# Sheet1_popravljena.net
KiCad netlist of a schematic drawn in Altium Designer
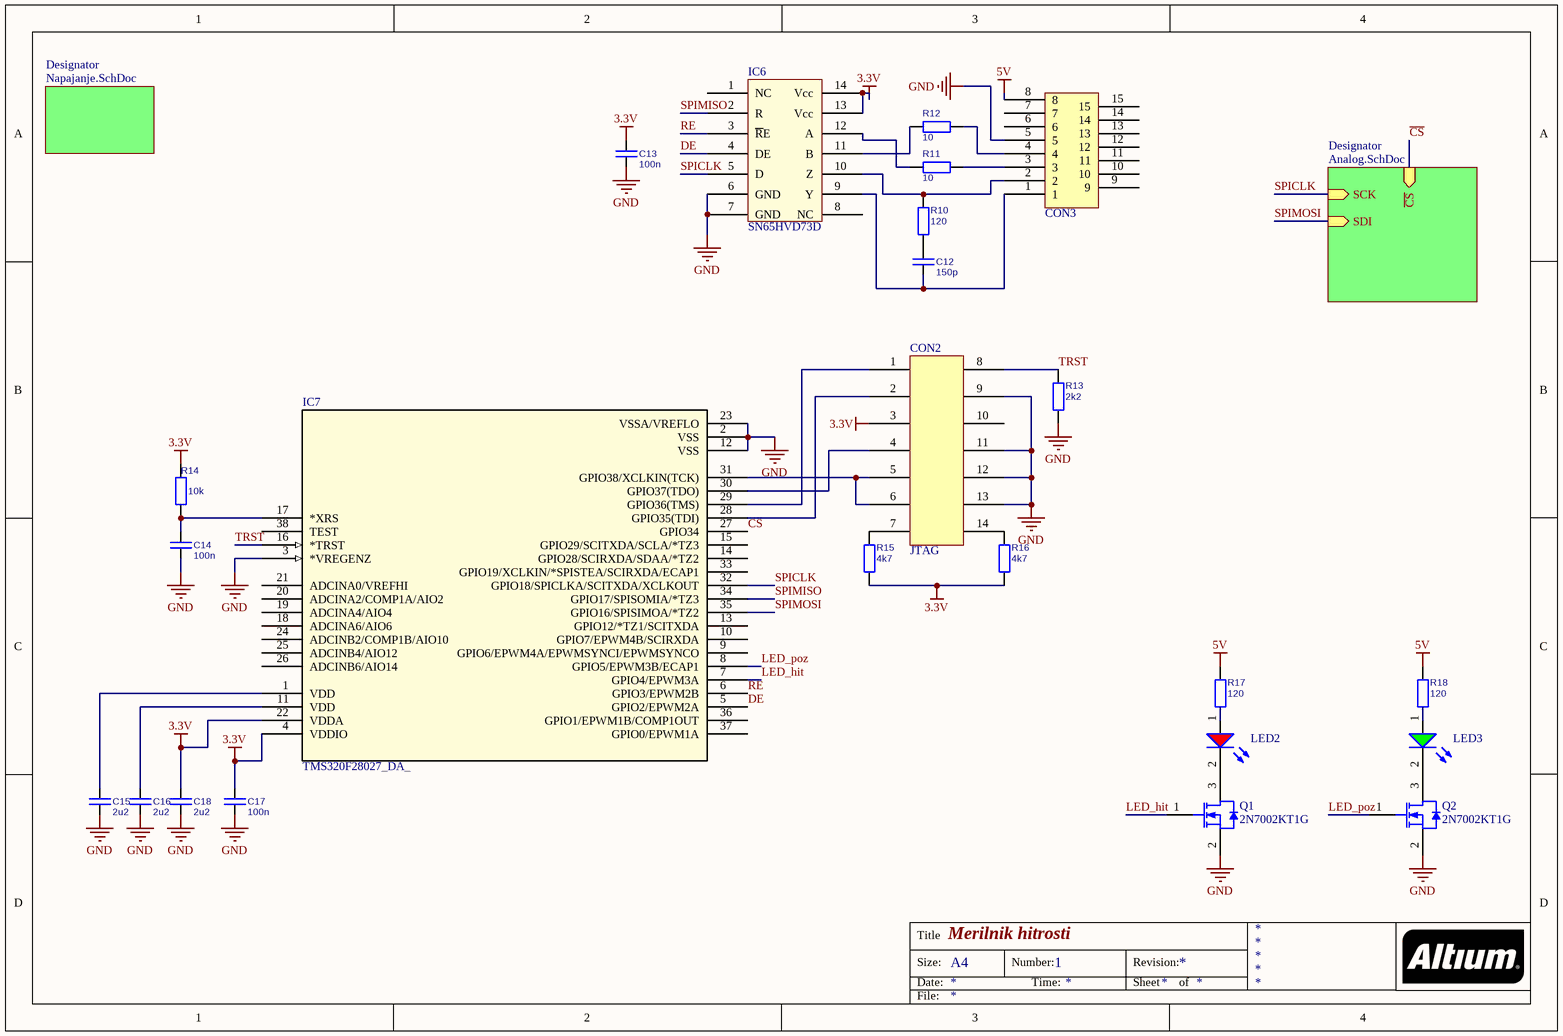
[diagram p0: Sheet1_popravljena.SchDoc]

(export (version "E")
  (design (tool "Eeschema 10.0.6"))
  (components
    (comp (ref "C12")
      (value "150p")
      (footprint "C0603")
      (description "Capacitor")
      (libsource (lib "General") (part "C"))
    )
    (comp (ref "C13")
      (value "100n")
      (footprint "C0603")
      (description "Capacitor")
      (libsource (lib "General") (part "C"))
    )
    (comp (ref "C14")
      (value "100n")
      (footprint "C0603")
      (description "Capacitor")
      (libsource (lib "General") (part "C"))
    )
    (comp (ref "C15")
      (value "2u2")
      (footprint "C0603")
      (description "Capacitor")
      (libsource (lib "General") (part "C"))
    )
    (comp (ref "C16")
      (value "2u2")
      (footprint "C0603")
      (description "Capacitor")
      (libsource (lib "General") (part "C"))
    )
    (comp (ref "C17")
      (value "100n")
      (footprint "C0603")
      (description "Capacitor")
      (libsource (lib "General") (part "C"))
    )
    (comp (ref "C18")
      (value "2u2")
      (footprint "C0603")
      (description "Capacitor")
      (libsource (lib "General") (part "C"))
    )
    (comp (ref "CON2")
      (value "JTAG")
      (footprint "JTAG micromatch")
      (libsource (lib "2016-11-04_16-51-30") (part "JTAG"))
    )
    (comp (ref "CON3")
      (value "DSUbConector")
      (footprint "DSUB conector")
      (libsource (lib "2016-11-04_16-51-30") (part "DSUbConector"))
    )
    (comp (ref "IC6") (value "SN65HVD73D") (libsource (lib "2016-11-04_16-51-30") (part "SN65HVD73D")))
    (comp (ref "IC7")
      (value "TMS320F28027_DA_")
      (footprint "TSOP65P810X120-38N")
      (description "Imported")
      (fields (field (name "MANUFACTURER_PART_NUMBER") "tms320f28027_da_38"))
      (libsource (lib "2016-11-04_16-51-30") (part "TMS320F28027_DA_"))
    )
    (comp (ref "LED2")
      (value "150060RS75000")
      (footprint "LED_0603_Red")
      (description "SMD mono-color Chip LED, WL-SMCW, Red")
      (fields
        (field (name "MANUFACTURER") "W黵th Elektronik eiSos GmbH")
        (field (name "CREATED BY") "Christin Otto")
      )
      (libsource (lib "WL-SMCW_rev15b") (part "WL-SMCW 0603  150060RS75000"))
    )
    (comp (ref "LED3")
      (value "150060VS75000")
      (footprint "LED_0603_Bright Green")
      (description "SMD mono-color Chip LED, WL-SMCW, Bright Green")
      (fields
        (field (name "MANUFACTURER") "W黵th Elektronik eiSos GmbH")
        (field (name "CREATED BY") "Christin Otto")
      )
      (libsource (lib "WL-SMCW_rev15b") (part "WL-SMCW 0603  150060VS75000"))
    )
    (comp (ref "Q1")
      (value "2N7002KT1G")
      (footprint "NXP-SOT23_N")
      (description "N-Channel Enhancement Mode Field-Effect Transistor, 50 V, 0.173 A, 3-Pin SOT23, Tape and Reel")
      (libsource (lib "NXP Semiconductors Standard MOSFETs") (part "BSN20,215"))
    )
    (comp (ref "Q2")
      (value "2N7002KT1G")
      (footprint "NXP-SOT23_N")
      (description "N-Channel Enhancement Mode Field-Effect Transistor, 50 V, 0.173 A, 3-Pin SOT23, Tape and Reel")
      (libsource (lib "NXP Semiconductors Standard MOSFETs") (part "BSN20,215"))
    )
    (comp (ref "R10")
      (value "120")
      (footprint "R0603")
      (description "R")
      (libsource (lib "General") (part "R"))
    )
    (comp (ref "R11")
      (value "10")
      (footprint "R0603")
      (description "R")
      (libsource (lib "General") (part "R"))
    )
    (comp (ref "R12")
      (value "10")
      (footprint "R0603")
      (description "R")
      (libsource (lib "General") (part "R"))
    )
    (comp (ref "R13")
      (value "2k2")
      (footprint "R0805")
      (description "R")
      (fields (field (name "Comment") "120"))
      (libsource (lib "General") (part "R"))
    )
    (comp (ref "R14")
      (value "10k")
      (footprint "R0805")
      (description "R")
      (fields (field (name "Comment") "120"))
      (libsource (lib "General") (part "R"))
    )
    (comp (ref "R15")
      (value "4k7")
      (footprint "R0805")
      (description "R")
      (libsource (lib "General") (part "R"))
    )
    (comp (ref "R16")
      (value "4k7")
      (footprint "R0805")
      (description "R")
      (libsource (lib "General") (part "R"))
    )
    (comp (ref "R17")
      (value "120")
      (footprint "R0805")
      (description "R")
      (libsource (lib "General") (part "R"))
    )
    (comp (ref "R18")
      (value "120")
      (footprint "R0805")
      (description "R")
      (libsource (lib "General") (part "R"))
    )
  )
  (nets
    (net (code "1") (name "/DE") (class "Default")
      (node (ref "IC6") (pin "4") (pinfunction "DE_4") (pintype "passive"))
      (node (ref "IC7") (pin "5") (pinfunction "GPIO2/EPWM2A_5") (pintype "passive"))
    )
    (net (code "2") (name "/LED_hit") (class "Default")
      (node (ref "IC7") (pin "7") (pinfunction "GPIO4/EPWM3A_7") (pintype "passive"))
      (node (ref "Q1") (pin "1") (pinfunction "G_1") (pintype "passive"))
    )
    (net (code "3") (name "/LED_poz") (class "Default")
      (node (ref "IC7") (pin "8") (pinfunction "GPIO5/EPWM3B/ECAP1_8") (pintype "passive"))
      (node (ref "Q2") (pin "1") (pinfunction "G_1") (pintype "passive"))
    )
    (net (code "4") (name "/RE") (class "Default")
      (node (ref "IC6") (pin "3") (pinfunction "~{R}E_3") (pintype "passive"))
      (node (ref "IC7") (pin "6") (pinfunction "GPIO3/EPWM2B_6") (pintype "passive"))
    )
    (net (code "5") (name "/SPICLK") (class "Default")
      (node (ref "IC6") (pin "5") (pinfunction "D_5") (pintype "passive"))
      (node (ref "IC7") (pin "32") (pinfunction "GPIO18/SPICLKA/SCITXDA/XCLKOUT_32") (pintype "passive"))
    )
    (net (code "6") (name "/SPIMISO") (class "Default")
      (node (ref "IC6") (pin "2") (pinfunction "R_2") (pintype "passive"))
      (node (ref "IC7") (pin "34") (pinfunction "GPIO17/SPISOMIA/*TZ3_34") (pintype "passive"))
    )
    (net (code "7") (name "/SPIMOSI") (class "Default")
      (node (ref "IC7") (pin "35") (pinfunction "GPIO16/SPISIMOA/*TZ2_35") (pintype "passive"))
    )
    (net (code "8") (name "/TRST") (class "Default")
      (node (ref "CON2") (pin "8") (pinfunction "8_8") (pintype "passive"))
      (node (ref "IC7") (pin "16") (pinfunction "*TRST_16") (pintype "input"))
      (node (ref "R13") (pin "2") (pintype "passive"))
    )
    (net (code "9") (name "/~{CS}") (class "Default")
      (node (ref "IC7") (pin "27") (pinfunction "GPIO34_27") (pintype "passive"))
    )
    (net (code "10") (name "3.3V") (class "Default")
      (node (ref "C13") (pin "1") (pinfunction "1_1") (pintype "passive"))
      (node (ref "C17") (pin "1") (pinfunction "1_1") (pintype "passive"))
      (node (ref "C18") (pin "1") (pinfunction "1_1") (pintype "passive"))
      (node (ref "CON2") (pin "3") (pinfunction "3_3") (pintype "passive"))
      (node (ref "IC6") (pin "13") (pinfunction "Vcc_13") (pintype "passive"))
      (node (ref "IC6") (pin "14") (pinfunction "Vcc_14") (pintype "passive"))
      (node (ref "IC7") (pin "22") (pinfunction "VDDA_22") (pintype "power_in"))
      (node (ref "IC7") (pin "4") (pinfunction "VDDIO_4") (pintype "power_in"))
      (node (ref "R14") (pin "1") (pintype "passive"))
      (node (ref "R15") (pin "1") (pintype "passive"))
      (node (ref "R16") (pin "1") (pintype "passive"))
    )
    (net (code "11") (name "5V") (class "Default")
      (node (ref "CON3") (pin "8") (pinfunction "8_8") (pintype "passive"))
      (node (ref "R17") (pin "1") (pintype "passive"))
      (node (ref "R18") (pin "1") (pintype "passive"))
    )
    (net (code "12") (name "GND") (class "Default")
      (node (ref "C13") (pin "2") (pinfunction "2_2") (pintype "passive"))
      (node (ref "C14") (pin "2") (pinfunction "2_2") (pintype "passive"))
      (node (ref "C15") (pin "2") (pinfunction "2_2") (pintype "passive"))
      (node (ref "C16") (pin "2") (pinfunction "2_2") (pintype "passive"))
      (node (ref "C17") (pin "2") (pinfunction "2_2") (pintype "passive"))
      (node (ref "C18") (pin "2") (pinfunction "2_2") (pintype "passive"))
      (node (ref "CON2") (pin "11") (pinfunction "11_11") (pintype "passive"))
      (node (ref "CON2") (pin "12") (pinfunction "12_12") (pintype "passive"))
      (node (ref "CON2") (pin "13") (pinfunction "13_13") (pintype "passive"))
      (node (ref "CON2") (pin "9") (pinfunction "9_9") (pintype "passive"))
      (node (ref "CON3") (pin "5") (pinfunction "5_5") (pintype "passive"))
      (node (ref "IC6") (pin "6") (pinfunction "GND_6") (pintype "passive"))
      (node (ref "IC6") (pin "7") (pinfunction "GND_7") (pintype "passive"))
      (node (ref "IC7") (pin "12") (pinfunction "VSS_12") (pintype "power_in"))
      (node (ref "IC7") (pin "2") (pinfunction "VSS_2") (pintype "power_in"))
      (node (ref "IC7") (pin "23") (pinfunction "VSSA/VREFLO_23") (pintype "power_in"))
      (node (ref "IC7") (pin "3") (pinfunction "*VREGENZ_3") (pintype "input"))
      (node (ref "Q1") (pin "2") (pinfunction "S_2") (pintype "passive"))
      (node (ref "Q2") (pin "2") (pinfunction "S_2") (pintype "passive"))
      (node (ref "R13") (pin "1") (pintype "passive"))
    )
    (net (code "13") (name "Net-(C12-Pad1)") (class "Default")
      (node (ref "C12") (pin "1") (pinfunction "1_1") (pintype "passive"))
      (node (ref "R10") (pin "2") (pintype "passive"))
    )
    (net (code "14") (name "Net-(C15-Pad1)") (class "Default")
      (node (ref "C15") (pin "1") (pinfunction "1_1") (pintype "passive"))
      (node (ref "IC7") (pin "1") (pinfunction "VDD_1") (pintype "power_in"))
    )
    (net (code "15") (name "Net-(C16-Pad1)") (class "Default")
      (node (ref "C16") (pin "1") (pinfunction "1_1") (pintype "passive"))
      (node (ref "IC7") (pin "11") (pinfunction "VDD_11") (pintype "power_in"))
    )
    (net (code "16") (name "Net-(CON2-Pad7)") (class "Default")
      (node (ref "CON2") (pin "7") (pinfunction "7_7") (pintype "passive"))
      (node (ref "R15") (pin "2") (pintype "passive"))
    )
    (net (code "17") (name "Net-(CON2-Pad14)") (class "Default")
      (node (ref "CON2") (pin "14") (pinfunction "14_14") (pintype "passive"))
      (node (ref "R16") (pin "2") (pintype "passive"))
    )
    (net (code "18") (name "Net-(CON3-Pad3)") (class "Default")
      (node (ref "CON3") (pin "3") (pinfunction "3_3") (pintype "passive"))
      (node (ref "R11") (pin "1") (pintype "passive"))
    )
    (net (code "19") (name "Net-(CON3-Pad4)") (class "Default")
      (node (ref "CON3") (pin "4") (pinfunction "4_4") (pintype "passive"))
      (node (ref "R12") (pin "1") (pintype "passive"))
    )
    (net (code "20") (name "Net-(IC6-A)") (class "Default")
      (node (ref "IC6") (pin "12") (pinfunction "A_12") (pintype "passive"))
      (node (ref "R11") (pin "2") (pintype "passive"))
    )
    (net (code "21") (name "Net-(IC6-B)") (class "Default")
      (node (ref "IC6") (pin "11") (pinfunction "B_11") (pintype "passive"))
      (node (ref "R12") (pin "2") (pintype "passive"))
    )
    (net (code "22") (name "Net-(IC6-Y)") (class "Default")
      (node (ref "C12") (pin "2") (pinfunction "2_2") (pintype "passive"))
      (node (ref "CON3") (pin "1") (pinfunction "1_1") (pintype "passive"))
      (node (ref "IC6") (pin "9") (pinfunction "Y_9") (pintype "passive"))
    )
    (net (code "23") (name "Net-(IC6-Z)") (class "Default")
      (node (ref "CON3") (pin "2") (pinfunction "2_2") (pintype "passive"))
      (node (ref "IC6") (pin "10") (pinfunction "Z_10") (pintype "passive"))
      (node (ref "R10") (pin "1") (pintype "passive"))
    )
    (net (code "24") (name "Net-(IC7-*XRS)") (class "Default")
      (node (ref "C14") (pin "1") (pinfunction "1_1") (pintype "passive"))
      (node (ref "IC7") (pin "17") (pinfunction "*XRS_17") (pintype "passive"))
      (node (ref "R14") (pin "2") (pintype "passive"))
    )
    (net (code "25") (name "Net-(IC7-GPIO35(TDI))") (class "Default")
      (node (ref "CON2") (pin "2") (pinfunction "2_2") (pintype "passive"))
      (node (ref "IC7") (pin "28") (pinfunction "GPIO35(TDI)_28") (pintype "passive"))
    )
    (net (code "26") (name "Net-(IC7-GPIO36(TMS))") (class "Default")
      (node (ref "CON2") (pin "1") (pinfunction "1_1") (pintype "passive"))
      (node (ref "IC7") (pin "29") (pinfunction "GPIO36(TMS)_29") (pintype "passive"))
    )
    (net (code "27") (name "Net-(IC7-GPIO37(TDO))") (class "Default")
      (node (ref "CON2") (pin "4") (pinfunction "4_4") (pintype "passive"))
      (node (ref "IC7") (pin "30") (pinfunction "GPIO37(TDO)_30") (pintype "passive"))
    )
    (net (code "28") (name "Net-(IC7-GPIO38{slash}XCLKIN(TCK))") (class "Default")
      (node (ref "CON2") (pin "5") (pinfunction "5_5") (pintype "passive"))
      (node (ref "CON2") (pin "6") (pinfunction "6_6") (pintype "passive"))
      (node (ref "IC7") (pin "31") (pinfunction "GPIO38/XCLKIN(TCK)_31") (pintype "passive"))
    )
    (net (code "29") (name "Net-(LED2-A)") (class "Default")
      (node (ref "LED2") (pin "1") (pinfunction "A_1") (pintype "passive"))
      (node (ref "R17") (pin "2") (pintype "passive"))
    )
    (net (code "30") (name "Net-(LED2-C)") (class "Default")
      (node (ref "LED2") (pin "2") (pinfunction "C_2") (pintype "passive"))
      (node (ref "Q1") (pin "3") (pinfunction "D_3") (pintype "passive"))
    )
    (net (code "31") (name "Net-(LED3-A)") (class "Default")
      (node (ref "LED3") (pin "1") (pinfunction "A_1") (pintype "passive"))
      (node (ref "R18") (pin "2") (pintype "passive"))
    )
    (net (code "32") (name "Net-(LED3-C)") (class "Default")
      (node (ref "LED3") (pin "2") (pinfunction "C_2") (pintype "passive"))
      (node (ref "Q2") (pin "3") (pinfunction "D_3") (pintype "passive"))
    )
    (net (code "33") (name "unconnected-(CON2-Pad10)") (class "Default")
      (node (ref "CON2") (pin "10") (pinfunction "10_10") (pintype "passive"))
    )
    (net (code "34") (name "unconnected-(CON3-Pad6)") (class "Default")
      (node (ref "CON3") (pin "6") (pinfunction "6_6") (pintype "passive"))
    )
    (net (code "35") (name "unconnected-(CON3-Pad7)") (class "Default")
      (node (ref "CON3") (pin "7") (pinfunction "7_7") (pintype "passive"))
    )
    (net (code "36") (name "unconnected-(CON3-Pad9)") (class "Default")
      (node (ref "CON3") (pin "9") (pinfunction "9_9") (pintype "passive"))
    )
    (net (code "37") (name "unconnected-(CON3-Pad10)") (class "Default")
      (node (ref "CON3") (pin "10") (pinfunction "10_10") (pintype "passive"))
    )
    (net (code "38") (name "unconnected-(CON3-Pad11)") (class "Default")
      (node (ref "CON3") (pin "11") (pinfunction "11_11") (pintype "passive"))
    )
    (net (code "39") (name "unconnected-(CON3-Pad12)") (class "Default")
      (node (ref "CON3") (pin "12") (pinfunction "12_12") (pintype "passive"))
    )
    (net (code "40") (name "unconnected-(CON3-Pad13)") (class "Default")
      (node (ref "CON3") (pin "13") (pinfunction "13_13") (pintype "passive"))
    )
    (net (code "41") (name "unconnected-(CON3-Pad14)") (class "Default")
      (node (ref "CON3") (pin "14") (pinfunction "14_14") (pintype "passive"))
    )
    (net (code "42") (name "unconnected-(CON3-Pad15)") (class "Default")
      (node (ref "CON3") (pin "15") (pinfunction "15_15") (pintype "passive"))
    )
    (net (code "43") (name "unconnected-(IC6-NC-Pad1)") (class "Default")
      (node (ref "IC6") (pin "1") (pinfunction "NC_1") (pintype "passive"))
    )
    (net (code "44") (name "unconnected-(IC6-NC-Pad8)") (class "Default")
      (node (ref "IC6") (pin "8") (pinfunction "NC_8") (pintype "passive"))
    )
    (net (code "45") (name "unconnected-(IC7-ADCINA0{slash}VREFHI-Pad21)") (class "Default")
      (node (ref "IC7") (pin "21") (pinfunction "ADCINA0/VREFHI_21") (pintype "passive"))
    )
    (net (code "46") (name "unconnected-(IC7-ADCINA2{slash}COMP1A{slash}AIO2-Pad20)") (class "Default")
      (node (ref "IC7") (pin "20") (pinfunction "ADCINA2/COMP1A/AIO2_20") (pintype "passive"))
    )
    (net (code "47") (name "unconnected-(IC7-ADCINA4{slash}AIO4-Pad19)") (class "Default")
      (node (ref "IC7") (pin "19") (pinfunction "ADCINA4/AIO4_19") (pintype "passive"))
    )
    (net (code "48") (name "unconnected-(IC7-ADCINA6{slash}AIO6-Pad18)") (class "Default")
      (node (ref "IC7") (pin "18") (pinfunction "ADCINA6/AIO6_18") (pintype "passive"))
    )
    (net (code "49") (name "unconnected-(IC7-ADCINB2{slash}COMP1B{slash}AIO10-Pad24)") (class "Default")
      (node (ref "IC7") (pin "24") (pinfunction "ADCINB2/COMP1B/AIO10_24") (pintype "passive"))
    )
    (net (code "50") (name "unconnected-(IC7-ADCINB4{slash}AIO12-Pad25)") (class "Default")
      (node (ref "IC7") (pin "25") (pinfunction "ADCINB4/AIO12_25") (pintype "passive"))
    )
    (net (code "51") (name "unconnected-(IC7-ADCINB6{slash}AIO14-Pad26)") (class "Default")
      (node (ref "IC7") (pin "26") (pinfunction "ADCINB6/AIO14_26") (pintype "passive"))
    )
    (net (code "52") (name "unconnected-(IC7-GPIO0{slash}EPWM1A-Pad37)") (class "Default")
      (node (ref "IC7") (pin "37") (pinfunction "GPIO0/EPWM1A_37") (pintype "passive"))
    )
    (net (code "53") (name "unconnected-(IC7-GPIO1{slash}EPWM1B{slash}COMP1OUT-Pad36)") (class "Default")
      (node (ref "IC7") (pin "36") (pinfunction "GPIO1/EPWM1B/COMP1OUT_36") (pintype "passive"))
    )
    (net (code "54") (name "unconnected-(IC7-GPIO6{slash}EPWM4A{slash}EPWMSYNCI{slash}EPWMSYNCO-Pad9)") (class "Default")
      (node (ref "IC7") (pin "9") (pinfunction "GPIO6/EPWM4A/EPWMSYNCI/EPWMSYNCO_9") (pintype "passive"))
    )
    (net (code "55") (name "unconnected-(IC7-GPIO7{slash}EPWM4B{slash}SCIRXDA-Pad10)") (class "Default")
      (node (ref "IC7") (pin "10") (pinfunction "GPIO7/EPWM4B/SCIRXDA_10") (pintype "passive"))
    )
    (net (code "56") (name "unconnected-(IC7-GPIO12{slash}*TZ1{slash}SCITXDA-Pad13)") (class "Default")
      (node (ref "IC7") (pin "13") (pinfunction "GPIO12/*TZ1/SCITXDA_13") (pintype "passive"))
    )
    (net (code "57") (name "unconnected-(IC7-GPIO19{slash}XCLKIN{slash}*SPISTEA{slash}SCIRXDA{slash}ECAP1-Pad33)") (class "Default")
      (node (ref "IC7") (pin "33") (pinfunction "GPIO19/XCLKIN/*SPISTEA/SCIRXDA/ECAP1_33") (pintype "passive"))
    )
    (net (code "58") (name "unconnected-(IC7-GPIO28{slash}SCIRXDA{slash}SDAA{slash}*TZ2-Pad14)") (class "Default")
      (node (ref "IC7") (pin "14") (pinfunction "GPIO28/SCIRXDA/SDAA/*TZ2_14") (pintype "passive"))
    )
    (net (code "59") (name "unconnected-(IC7-GPIO29{slash}SCITXDA{slash}SCLA{slash}*TZ3-Pad15)") (class "Default")
      (node (ref "IC7") (pin "15") (pinfunction "GPIO29/SCITXDA/SCLA/*TZ3_15") (pintype "passive"))
    )
    (net (code "60") (name "unconnected-(IC7-TEST-Pad38)") (class "Default")
      (node (ref "IC7") (pin "38") (pinfunction "TEST_38") (pintype "passive"))
    )
  )
)
